# base.net
KiCad netlist of a schematic drawn in Altium Designer
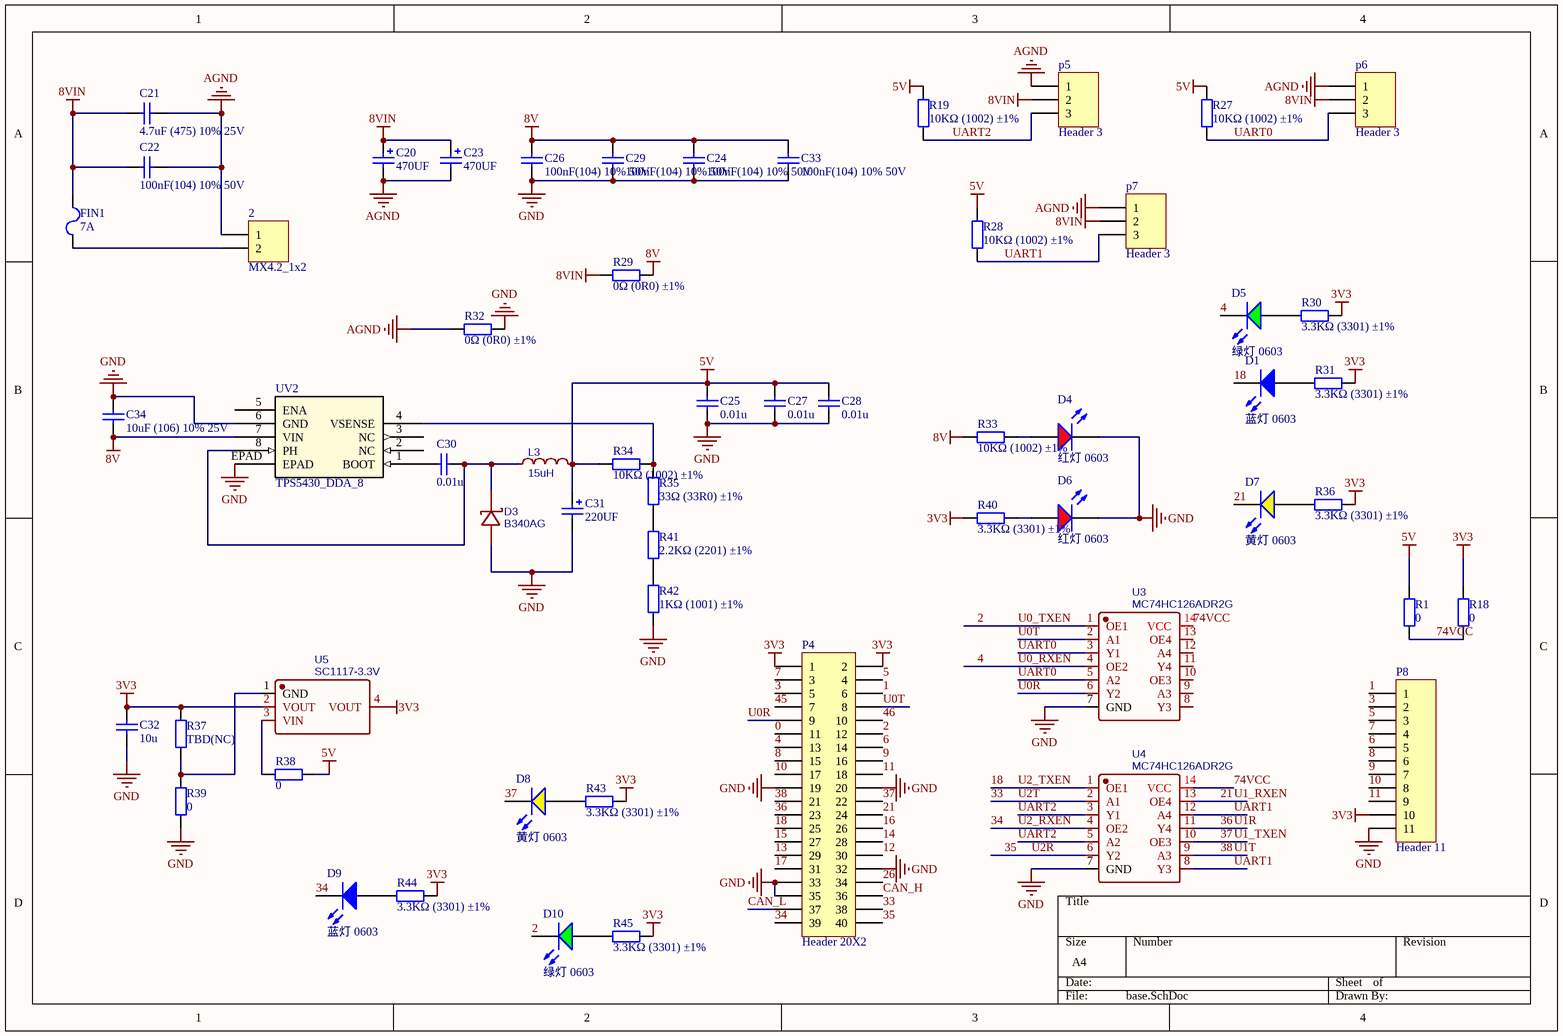
[diagram p0: base.SchDoc]

(export (version "E")
  (design (tool "Eeschema 10.0.6"))
  (components
    (comp (ref "2") (value "MX4.2_1x2") (footprint "MX4.2_1x2") (libsource (lib "Schlib") (part "MX4.2_1x2")))
    (comp (ref "C20")
      (value "470UF")
      (footprint "CAP-SMD_BD8.0-L8.3-W8.3-LS9.0-FD")
      (libsource (lib "Schlib") (part "C_RB-470UF/25V_5X10"))
    )
    (comp (ref "C21")
      (value "4.7uF (475) 10% 25V")
      (footprint "LC-0805_C")
      (description "贴片电容")
      (libsource (lib "Miscellaneous Devices LC") (part "0805 4.7uF (475) 10% 25V"))
    )
    (comp (ref "C22")
      (value "100nF(104) 10% 50V")
      (footprint "LC-0805_C")
      (description "贴片电容")
      (libsource (lib "Miscellaneous Devices LC") (part "0805 100nF(104) 10% 50V"))
    )
    (comp (ref "C23")
      (value "470UF")
      (footprint "CAP-SMD_BD8.0-L8.3-W8.3-LS9.0-FD")
      (libsource (lib "Schlib") (part "C_RB-470UF/25V_5X10"))
    )
    (comp (ref "C24")
      (value "100nF(104) 10% 50V")
      (footprint "LC-0805_C")
      (description "贴片电容")
      (libsource (lib "Miscellaneous Devices LC") (part "0805 100nF(104) 10% 50V"))
    )
    (comp (ref "C25") (value "0.01u") (footprint "C0603") (libsource (lib "Schlib") (part "CAP_0805")))
    (comp (ref "C26")
      (value "100nF(104) 10% 50V")
      (footprint "LC-0805_C")
      (description "贴片电容")
      (libsource (lib "Miscellaneous Devices LC") (part "0805 100nF(104) 10% 50V"))
    )
    (comp (ref "C27") (value "0.01u") (footprint "C0603") (libsource (lib "Schlib") (part "CAP_0805")))
    (comp (ref "C28") (value "0.01u") (footprint "C0603") (libsource (lib "Schlib") (part "CAP_0805")))
    (comp (ref "C29")
      (value "100nF(104) 10% 50V")
      (footprint "LC-0805_C")
      (description "贴片电容")
      (libsource (lib "Miscellaneous Devices LC") (part "0805 100nF(104) 10% 50V"))
    )
    (comp (ref "C30") (value "0.01u") (footprint "C0603") (libsource (lib "Schlib") (part "CAP_0805")))
    (comp (ref "C31")
      (value "220UF")
      (footprint "SMD,6.3x7.7mm")
      (libsource (lib "Schlib") (part "C_RB-470UF/25V_5X10"))
    )
    (comp (ref "C32") (value "10u") (footprint "C0603") (libsource (lib "Schlib") (part "CAP_0805")))
    (comp (ref "C33")
      (value "100nF(104) 10% 50V")
      (footprint "LC-0805_C")
      (description "贴片电容")
      (libsource (lib "Miscellaneous Devices LC") (part "0805 100nF(104) 10% 50V"))
    )
    (comp (ref "C34")
      (value "10uF (106) 10% 25V")
      (footprint "LC-0805_C")
      (description "贴片电容")
      (libsource (lib "Miscellaneous Devices LC") (part "0805 10uF (106) 10% 25V"))
    )
    (comp (ref "D1")
      (value "蓝灯 0603")
      (footprint "LC-0603_LED_S1")
      (description "发光二极管")
      (libsource (lib "Miscellaneous Devices LC") (part "0603 蓝灯"))
    )
    (comp (ref "D3")
      (value "B340AG")
      (footprint "SMA_L4.4-W2.6-LS5.0-RD")
      (fields (field (name "BOM_SUPPLIER PART") "C433997") (field (name "CONTRIBUTOR") "LCSC"))
      (libsource (lib "altium-import") (part "root_3_B340AG_"))
    )
    (comp (ref "D4")
      (value "红灯 0603")
      (footprint "LC-0603_LED_S1")
      (description "发光二极管")
      (libsource (lib "Miscellaneous Devices LC") (part "0603 红灯"))
    )
    (comp (ref "D5")
      (value "绿灯 0603")
      (footprint "LC-0603_LED_S1")
      (description "发光二极管")
      (libsource (lib "Miscellaneous Devices LC") (part "0603 绿灯"))
    )
    (comp (ref "D6")
      (value "红灯 0603")
      (footprint "LC-0603_LED_S1")
      (description "发光二极管")
      (libsource (lib "Miscellaneous Devices LC") (part "0603 红灯"))
    )
    (comp (ref "D7")
      (value "黄灯 0603")
      (footprint "LC-0603_LED_S1")
      (description "发光二极管")
      (libsource (lib "Miscellaneous Devices LC") (part "0603 黄灯"))
    )
    (comp (ref "D8")
      (value "黄灯 0603")
      (footprint "LC-0603_LED_S1")
      (description "发光二极管")
      (libsource (lib "Miscellaneous Devices LC") (part "0603 黄灯"))
    )
    (comp (ref "D9")
      (value "蓝灯 0603")
      (footprint "LC-0603_LED_S1")
      (description "发光二极管")
      (libsource (lib "Miscellaneous Devices LC") (part "0603 蓝灯"))
    )
    (comp (ref "D10")
      (value "绿灯 0603")
      (footprint "LC-0603_LED_S1")
      (description "发光二极管")
      (libsource (lib "Miscellaneous Devices LC") (part "0603 绿灯"))
    )
    (comp (ref "FIN1") (value "7A") (footprint "2512") (libsource (lib "Schlib") (part "Fuse")))
    (comp (ref "L3")
      (value "15uH")
      (footprint "电感")
      (fields
        (field (name "BOM_SUPPLIER PART") "C354559")
        (field (name "BOM_MANUFACTURER PART") "CKCS3012-15uH/M")
        (field (name "CONTRIBUTOR") "LCSC")
      )
      (libsource (lib "PCB_Project") (part "15uH"))
    )
    (comp (ref "P4")
      (value "Header 20X2")
      (footprint "ESP-BORD")
      (description "Header, 20-Pin, Dual row")
      (fields (field (name "PUBLISHER") "Altium Limited"))
      (libsource (lib "Miscellaneous Connectors") (part "Header 20X2"))
    )
    (comp (ref "p5")
      (value "Header 3")
      (footprint "PH2.0-LI-3P")
      (description "Header, 3-Pin")
      (fields (field (name "PUBLISHER") "Altium Limited"))
      (libsource (lib "Miscellaneous Connectors") (part "Header 3"))
    )
    (comp (ref "p6")
      (value "Header 3")
      (footprint "PH2.0-LI-3P")
      (description "Header, 3-Pin")
      (fields (field (name "PUBLISHER") "Altium Limited"))
      (libsource (lib "Miscellaneous Connectors") (part "Header 3"))
    )
    (comp (ref "p7")
      (value "Header 3")
      (footprint "PH2.0-LI-3P")
      (description "Header, 3-Pin")
      (fields (field (name "PUBLISHER") "Altium Limited"))
      (libsource (lib "Miscellaneous Connectors") (part "Header 3"))
    )
    (comp (ref "P8")
      (value "Header 11")
      (footprint "HDR1X11")
      (description "Header, 11-Pin")
      (fields (field (name "PUBLISHER") "Altium Limited"))
      (libsource (lib "Miscellaneous Connectors") (part "Header 11"))
    )
    (comp (ref "R1") (value "0") (footprint "R0603") (libsource (lib "Schlib") (part "RES_0805")))
    (comp (ref "R18") (value "0") (footprint "R0603") (libsource (lib "Schlib") (part "RES_0805")))
    (comp (ref "R19")
      (value "10KΩ (1002) ±1%")
      (footprint "LC-0402_R")
      (description "贴片电阻")
      (libsource (lib "Miscellaneous Devices LC") (part "0402 10KΩ (1002) 1%"))
    )
    (comp (ref "R27")
      (value "10KΩ (1002) ±1%")
      (footprint "LC-0402_R")
      (description "贴片电阻")
      (libsource (lib "") (part "0402 10KΩ (1002) 1%_2"))
    )
    (comp (ref "R28")
      (value "10KΩ (1002) ±1%")
      (footprint "LC-0402_R")
      (description "贴片电阻")
      (libsource (lib "") (part "0402 10KΩ (1002) 1%_2"))
    )
    (comp (ref "R29")
      (value "0Ω (0R0) ±1%")
      (footprint "LC-0805_R")
      (description "贴片电阻")
      (libsource (lib "Miscellaneous Devices LC") (part "0805 0Ω (0R0) 1%"))
    )
    (comp (ref "R30")
      (value "3.3KΩ (3301) ±1%")
      (footprint "LC-0402_R")
      (description "贴片电阻")
      (libsource (lib "Miscellaneous Devices LC") (part "0402 3.3KΩ (3301) 1%"))
    )
    (comp (ref "R31")
      (value "3.3KΩ (3301) ±1%")
      (footprint "LC-0402_R")
      (description "贴片电阻")
      (libsource (lib "Miscellaneous Devices LC") (part "0402 3.3KΩ (3301) 1%"))
    )
    (comp (ref "R32")
      (value "0Ω (0R0) ±1%")
      (footprint "LC-0805_R")
      (description "贴片电阻")
      (libsource (lib "Miscellaneous Devices LC") (part "0805 0Ω (0R0) 1%"))
    )
    (comp (ref "R33")
      (value "10KΩ (1002) ±1%")
      (footprint "LC-0402_R")
      (description "贴片电阻")
      (libsource (lib "") (part "0402 10KΩ (1002) 1%_1"))
    )
    (comp (ref "R34")
      (value "10KΩ (1002) ±1%")
      (footprint "LC-0805_R")
      (description "贴片电阻")
      (libsource (lib "Miscellaneous Devices LC") (part "0805 10KΩ (1002) 1%"))
    )
    (comp (ref "R35")
      (value "33Ω (33R0) ±1%")
      (footprint "LC-0805_R")
      (description "贴片电阻")
      (libsource (lib "Miscellaneous Devices LC") (part "0805 33Ω (33R0) 1%"))
    )
    (comp (ref "R36")
      (value "3.3KΩ (3301) ±1%")
      (footprint "LC-0402_R")
      (description "贴片电阻")
      (libsource (lib "Miscellaneous Devices LC") (part "0402 3.3KΩ (3301) 1%"))
    )
    (comp (ref "R37") (value "TBD(NC)") (footprint "R0603") (libsource (lib "") (part "RES_0805_1")))
    (comp (ref "R38") (value "0") (footprint "R0603") (libsource (lib "") (part "RES_0805_2")))
    (comp (ref "R39") (value "0") (footprint "R0603") (libsource (lib "Schlib") (part "RES_0805")))
    (comp (ref "R40")
      (value "3.3KΩ (3301) ±1%")
      (footprint "LC-0402_R")
      (description "贴片电阻")
      (libsource (lib "Miscellaneous Devices LC") (part "0402 3.3KΩ (3301) 1%"))
    )
    (comp (ref "R41")
      (value "2.2KΩ (2201) ±1%")
      (footprint "LC-0805_R")
      (description "贴片电阻")
      (libsource (lib "Miscellaneous Devices LC") (part "0805 2.2KΩ (2201) 1%"))
    )
    (comp (ref "R42")
      (value "1KΩ (1001) ±1%")
      (footprint "LC-0805_R")
      (description "贴片电阻")
      (libsource (lib "Miscellaneous Devices LC") (part "0805 1KΩ (1001) 1%"))
    )
    (comp (ref "R43")
      (value "3.3KΩ (3301) ±1%")
      (footprint "LC-0402_R")
      (description "贴片电阻")
      (libsource (lib "Miscellaneous Devices LC") (part "0402 3.3KΩ (3301) 1%"))
    )
    (comp (ref "R44")
      (value "3.3KΩ (3301) ±1%")
      (footprint "LC-0402_R")
      (description "贴片电阻")
      (libsource (lib "Miscellaneous Devices LC") (part "0402 3.3KΩ (3301) 1%"))
    )
    (comp (ref "R45")
      (value "3.3KΩ (3301) ±1%")
      (footprint "LC-0402_R")
      (description "贴片电阻")
      (libsource (lib "Miscellaneous Devices LC") (part "0402 3.3KΩ (3301) 1%"))
    )
    (comp (ref "U3")
      (value "MC74HC126ADR2G")
      (footprint "SOIC-14_L8.7-W3.9-P1.27-LS6.0-BL")
      (fields (field (name "BOM_SUPPLIER PART") "C233530") (field (name "CONTRIBUTOR") "LCSC"))
      (libsource (lib "altium-import") (part "root_0_MC74HC126ADR2G_"))
    )
    (comp (ref "U4")
      (value "MC74HC126ADR2G")
      (footprint "SOIC-14_L8.7-W3.9-P1.27-LS6.0-BL")
      (fields (field (name "BOM_SUPPLIER PART") "C233530") (field (name "CONTRIBUTOR") "LCSC"))
      (libsource (lib "altium-import") (part "root_0_MC74HC126ADR2G_"))
    )
    (comp (ref "U5")
      (value "SC1117-3.3V")
      (footprint "SOT-223_L6.5-W3.5-P2.30-LS7.0-BR")
      (fields (field (name "BOM_SUPPLIER PART") "C173386") (field (name "CONTRIBUTOR") "LCSC"))
      (libsource (lib "altium-import") (part "root_0_SC1117-3.3V_"))
    )
    (comp (ref "UV2")
      (value "TPS5430_DDA_8")
      (footprint "DDA8_3P1X2P4")
      (description "Imported")
      (fields
        (field (name "MANUFACTURER_PART_NUMBER") "tps5430_dda_8")
        (field (name "GENERIC_PART_NUMBER") "TPS5430")
      )
      (libsource (lib "TPS5430") (part "TPS5430_DDA_8"))
    )
  )
  (nets
    (net (code "1") (name "/0") (class "Default")
      (node (ref "P4") (pin "11") (pinfunction "11_11") (pintype "passive"))
    )
    (net (code "2") (name "/1") (class "Default")
      (node (ref "P4") (pin "6") (pinfunction "6_6") (pintype "passive"))
      (node (ref "P8") (pin "1") (pinfunction "1_1") (pintype "passive"))
    )
    (net (code "3") (name "/2") (class "Default")
      (node (ref "D10") (pin "K") (pinfunction "K_K") (pintype "passive"))
      (node (ref "P4") (pin "12") (pinfunction "12_12") (pintype "passive"))
      (node (ref "U3") (pin "1") (pinfunction "OE1_1") (pintype "passive"))
    )
    (net (code "4") (name "/3") (class "Default")
      (node (ref "P4") (pin "5") (pinfunction "5_5") (pintype "passive"))
      (node (ref "P8") (pin "2") (pinfunction "2_2") (pintype "passive"))
    )
    (net (code "5") (name "/4") (class "Default")
      (node (ref "D5") (pin "K") (pinfunction "K_K") (pintype "passive"))
      (node (ref "P4") (pin "13") (pinfunction "13_13") (pintype "passive"))
      (node (ref "U3") (pin "4") (pinfunction "OE2_4") (pintype "passive"))
    )
    (net (code "6") (name "/5") (class "Default")
      (node (ref "P4") (pin "4") (pinfunction "4_4") (pintype "passive"))
      (node (ref "P8") (pin "3") (pinfunction "3_3") (pintype "passive"))
    )
    (net (code "7") (name "/6") (class "Default")
      (node (ref "P4") (pin "14") (pinfunction "14_14") (pintype "passive"))
      (node (ref "P8") (pin "5") (pinfunction "5_5") (pintype "passive"))
    )
    (net (code "8") (name "/7") (class "Default")
      (node (ref "P4") (pin "3") (pinfunction "3_3") (pintype "passive"))
      (node (ref "P8") (pin "4") (pinfunction "4_4") (pintype "passive"))
    )
    (net (code "9") (name "/8") (class "Default")
      (node (ref "P4") (pin "15") (pinfunction "15_15") (pintype "passive"))
      (node (ref "P8") (pin "6") (pinfunction "6_6") (pintype "passive"))
    )
    (net (code "10") (name "/9") (class "Default")
      (node (ref "P4") (pin "16") (pinfunction "16_16") (pintype "passive"))
      (node (ref "P8") (pin "7") (pinfunction "7_7") (pintype "passive"))
    )
    (net (code "11") (name "/10") (class "Default")
      (node (ref "P4") (pin "17") (pinfunction "17_17") (pintype "passive"))
      (node (ref "P8") (pin "8") (pinfunction "8_8") (pintype "passive"))
    )
    (net (code "12") (name "/11") (class "Default")
      (node (ref "P4") (pin "18") (pinfunction "18_18") (pintype "passive"))
      (node (ref "P8") (pin "9") (pinfunction "9_9") (pintype "passive"))
    )
    (net (code "13") (name "/12") (class "Default")
      (node (ref "P4") (pin "30") (pinfunction "30_30") (pintype "passive"))
    )
    (net (code "14") (name "/13") (class "Default")
      (node (ref "P4") (pin "29") (pinfunction "29_29") (pintype "passive"))
    )
    (net (code "15") (name "/14") (class "Default")
      (node (ref "P4") (pin "28") (pinfunction "28_28") (pintype "passive"))
    )
    (net (code "16") (name "/15") (class "Default")
      (node (ref "P4") (pin "27") (pinfunction "27_27") (pintype "passive"))
    )
    (net (code "17") (name "/16") (class "Default")
      (node (ref "P4") (pin "26") (pinfunction "26_26") (pintype "passive"))
    )
    (net (code "18") (name "/17") (class "Default")
      (node (ref "P4") (pin "31") (pinfunction "31_31") (pintype "passive"))
    )
    (net (code "19") (name "/18") (class "Default")
      (node (ref "D1") (pin "K") (pinfunction "K_K") (pintype "passive"))
      (node (ref "P4") (pin "25") (pinfunction "25_25") (pintype "passive"))
      (node (ref "U4") (pin "1") (pinfunction "OE1_1") (pintype "passive"))
    )
    (net (code "20") (name "/21") (class "Default")
      (node (ref "D7") (pin "K") (pinfunction "K_K") (pintype "passive"))
      (node (ref "P4") (pin "24") (pinfunction "24_24") (pintype "passive"))
      (node (ref "U4") (pin "13") (pinfunction "OE4_13") (pintype "passive"))
    )
    (net (code "21") (name "/26") (class "Default")
      (node (ref "P4") (pin "34") (pinfunction "34_34") (pintype "passive"))
    )
    (net (code "22") (name "/33") (class "Default")
      (node (ref "P4") (pin "38") (pinfunction "38_38") (pintype "passive"))
      (node (ref "U4") (pin "2") (pinfunction "A1_2") (pintype "passive"))
    )
    (net (code "23") (name "/34") (class "Default")
      (node (ref "D9") (pin "K") (pinfunction "K_K") (pintype "passive"))
      (node (ref "P4") (pin "39") (pinfunction "39_39") (pintype "passive"))
      (node (ref "U4") (pin "4") (pinfunction "OE2_4") (pintype "passive"))
    )
    (net (code "24") (name "/35") (class "Default")
      (node (ref "P4") (pin "40") (pinfunction "40_40") (pintype "passive"))
      (node (ref "U4") (pin "6") (pinfunction "Y2_6") (pintype "passive"))
    )
    (net (code "25") (name "/36") (class "Default")
      (node (ref "P4") (pin "23") (pinfunction "23_23") (pintype "passive"))
      (node (ref "U4") (pin "11") (pinfunction "Y4_11") (pintype "passive"))
    )
    (net (code "26") (name "/37") (class "Default")
      (node (ref "D8") (pin "K") (pinfunction "K_K") (pintype "passive"))
      (node (ref "P4") (pin "22") (pinfunction "22_22") (pintype "passive"))
      (node (ref "U4") (pin "10") (pinfunction "OE3_10") (pintype "passive"))
    )
    (net (code "27") (name "/38") (class "Default")
      (node (ref "P4") (pin "21") (pinfunction "21_21") (pintype "passive"))
      (node (ref "U4") (pin "9") (pinfunction "A3_9") (pintype "passive"))
    )
    (net (code "28") (name "/45") (class "Default")
      (node (ref "P4") (pin "7") (pinfunction "7_7") (pintype "passive"))
    )
    (net (code "29") (name "/46") (class "Default")
      (node (ref "P4") (pin "10") (pinfunction "10_10") (pintype "passive"))
    )
    (net (code "30") (name "/74VCC") (class "Default")
      (node (ref "R1") (pin "1") (pinfunction "1_1") (pintype "passive"))
      (node (ref "R18") (pin "1") (pinfunction "1_1") (pintype "passive"))
      (node (ref "U3") (pin "14") (pinfunction "VCC_14") (pintype "passive"))
      (node (ref "U4") (pin "14") (pinfunction "VCC_14") (pintype "passive"))
    )
    (net (code "31") (name "/CAN_H") (class "Default")
      (node (ref "P4") (pin "36") (pinfunction "36_36") (pintype "passive"))
    )
    (net (code "32") (name "/CAN_L") (class "Default")
      (node (ref "P4") (pin "37") (pinfunction "37_37") (pintype "passive"))
    )
    (net (code "33") (name "/U0R") (class "Default")
      (node (ref "P4") (pin "9") (pinfunction "9_9") (pintype "passive"))
      (node (ref "U3") (pin "6") (pinfunction "Y2_6") (pintype "passive"))
    )
    (net (code "34") (name "/U0T") (class "Default")
      (node (ref "P4") (pin "8") (pinfunction "8_8") (pintype "passive"))
      (node (ref "U3") (pin "2") (pinfunction "A1_2") (pintype "passive"))
    )
    (net (code "35") (name "/UART0") (class "Default")
      (node (ref "R27") (pin "1") (pinfunction "1_1") (pintype "passive"))
      (node (ref "U3") (pin "3") (pinfunction "Y1_3") (pintype "passive"))
      (node (ref "U3") (pin "5") (pinfunction "A2_5") (pintype "passive"))
      (node (ref "p6") (pin "3") (pinfunction "3_3") (pintype "passive"))
    )
    (net (code "36") (name "/UART1") (class "Default")
      (node (ref "R28") (pin "1") (pinfunction "1_1") (pintype "passive"))
      (node (ref "U4") (pin "12") (pinfunction "A4_12") (pintype "passive"))
      (node (ref "U4") (pin "8") (pinfunction "Y3_8") (pintype "passive"))
      (node (ref "p7") (pin "3") (pinfunction "3_3") (pintype "passive"))
    )
    (net (code "37") (name "/UART2") (class "Default")
      (node (ref "R19") (pin "2") (pinfunction "2_2") (pintype "passive"))
      (node (ref "U4") (pin "3") (pinfunction "Y1_3") (pintype "passive"))
      (node (ref "U4") (pin "5") (pinfunction "A2_5") (pintype "passive"))
      (node (ref "p5") (pin "3") (pinfunction "3_3") (pintype "passive"))
    )
    (net (code "38") (name "3V3") (class "Default")
      (node (ref "C32") (pin "2") (pinfunction "2_2") (pintype "passive"))
      (node (ref "P4") (pin "1") (pinfunction "1_1") (pintype "passive"))
      (node (ref "P4") (pin "2") (pinfunction "2_2") (pintype "passive"))
      (node (ref "P8") (pin "10") (pinfunction "10_10") (pintype "passive"))
      (node (ref "R18") (pin "2") (pinfunction "2_2") (pintype "passive"))
      (node (ref "R30") (pin "2") (pinfunction "2_2") (pintype "passive"))
      (node (ref "R31") (pin "2") (pinfunction "2_2") (pintype "passive"))
      (node (ref "R36") (pin "2") (pinfunction "2_2") (pintype "passive"))
      (node (ref "R37") (pin "1") (pinfunction "1_1") (pintype "passive"))
      (node (ref "R40") (pin "1") (pinfunction "1_1") (pintype "passive"))
      (node (ref "R43") (pin "2") (pinfunction "2_2") (pintype "passive"))
      (node (ref "R44") (pin "2") (pinfunction "2_2") (pintype "passive"))
      (node (ref "R45") (pin "2") (pinfunction "2_2") (pintype "passive"))
      (node (ref "U5") (pin "2") (pinfunction "VOUT_2") (pintype "passive"))
      (node (ref "U5") (pin "4") (pinfunction "VOUT_4") (pintype "passive"))
    )
    (net (code "39") (name "5V") (class "Default")
      (node (ref "C25") (pin "1") (pinfunction "1_1") (pintype "passive"))
      (node (ref "C27") (pin "1") (pinfunction "1_1") (pintype "passive"))
      (node (ref "C28") (pin "2") (pinfunction "2_2") (pintype "passive"))
      (node (ref "C31") (pin "1") (pinfunction "1_1") (pintype "passive"))
      (node (ref "L3") (pin "2") (pinfunction "2_2") (pintype "passive"))
      (node (ref "R1") (pin "2") (pinfunction "2_2") (pintype "passive"))
      (node (ref "R19") (pin "1") (pinfunction "1_1") (pintype "passive"))
      (node (ref "R27") (pin "2") (pinfunction "2_2") (pintype "passive"))
      (node (ref "R28") (pin "2") (pinfunction "2_2") (pintype "passive"))
      (node (ref "R34") (pin "1") (pinfunction "1_1") (pintype "passive"))
      (node (ref "R38") (pin "1") (pinfunction "1_1") (pintype "passive"))
    )
    (net (code "40") (name "8V") (class "Default")
      (node (ref "C24") (pin "2") (pinfunction "2_2") (pintype "passive"))
      (node (ref "C26") (pin "2") (pinfunction "2_2") (pintype "passive"))
      (node (ref "C29") (pin "2") (pinfunction "2_2") (pintype "passive"))
      (node (ref "C33") (pin "2") (pinfunction "2_2") (pintype "passive"))
      (node (ref "C34") (pin "1") (pinfunction "1_1") (pintype "passive"))
      (node (ref "R29") (pin "2") (pinfunction "2_2") (pintype "passive"))
      (node (ref "R33") (pin "1") (pinfunction "1_1") (pintype "passive"))
      (node (ref "UV2") (pin "7") (pinfunction "VIN_7") (pintype "passive"))
    )
    (net (code "41") (name "8VIN") (class "Default")
      (node (ref "C20") (pin "1") (pinfunction "1_1") (pintype "passive"))
      (node (ref "C21") (pin "1") (pinfunction "1_1") (pintype "passive"))
      (node (ref "C22") (pin "1") (pinfunction "1_1") (pintype "passive"))
      (node (ref "C23") (pin "1") (pinfunction "1_1") (pintype "passive"))
      (node (ref "FIN1") (pin "2") (pinfunction "2_2") (pintype "passive"))
      (node (ref "R29") (pin "1") (pinfunction "1_1") (pintype "passive"))
      (node (ref "p5") (pin "2") (pinfunction "2_2") (pintype "passive"))
      (node (ref "p6") (pin "2") (pinfunction "2_2") (pintype "passive"))
      (node (ref "p7") (pin "2") (pinfunction "2_2") (pintype "passive"))
    )
    (net (code "42") (name "AGND") (class "Default")
      (node (ref "2") (pin "1") (pinfunction "1_1") (pintype "passive"))
      (node (ref "C20") (pin "2") (pinfunction "2_2") (pintype "passive"))
      (node (ref "C21") (pin "2") (pinfunction "2_2") (pintype "passive"))
      (node (ref "C22") (pin "2") (pinfunction "2_2") (pintype "passive"))
      (node (ref "C23") (pin "2") (pinfunction "2_2") (pintype "passive"))
      (node (ref "R32") (pin "1") (pinfunction "1_1") (pintype "passive"))
      (node (ref "p5") (pin "1") (pinfunction "1_1") (pintype "passive"))
      (node (ref "p6") (pin "1") (pinfunction "1_1") (pintype "passive"))
      (node (ref "p7") (pin "1") (pinfunction "1_1") (pintype "passive"))
    )
    (net (code "43") (name "GND") (class "Default")
      (node (ref "C24") (pin "1") (pinfunction "1_1") (pintype "passive"))
      (node (ref "C25") (pin "2") (pinfunction "2_2") (pintype "passive"))
      (node (ref "C26") (pin "1") (pinfunction "1_1") (pintype "passive"))
      (node (ref "C27") (pin "2") (pinfunction "2_2") (pintype "passive"))
      (node (ref "C28") (pin "1") (pinfunction "1_1") (pintype "passive"))
      (node (ref "C29") (pin "1") (pinfunction "1_1") (pintype "passive"))
      (node (ref "C31") (pin "2") (pinfunction "2_2") (pintype "passive"))
      (node (ref "C32") (pin "1") (pinfunction "1_1") (pintype "passive"))
      (node (ref "C33") (pin "1") (pinfunction "1_1") (pintype "passive"))
      (node (ref "C34") (pin "2") (pinfunction "2_2") (pintype "passive"))
      (node (ref "D3") (pin "2") (pinfunction "A_2") (pintype "passive"))
      (node (ref "D4") (pin "K") (pinfunction "K_K") (pintype "passive"))
      (node (ref "D6") (pin "K") (pinfunction "K_K") (pintype "passive"))
      (node (ref "P4") (pin "19") (pinfunction "19_19") (pintype "passive"))
      (node (ref "P4") (pin "20") (pinfunction "20_20") (pintype "passive"))
      (node (ref "P4") (pin "32") (pinfunction "32_32") (pintype "passive"))
      (node (ref "P4") (pin "33") (pinfunction "33_33") (pintype "passive"))
      (node (ref "P4") (pin "35") (pinfunction "35_35") (pintype "passive"))
      (node (ref "P8") (pin "11") (pinfunction "11_11") (pintype "passive"))
      (node (ref "R32") (pin "2") (pinfunction "2_2") (pintype "passive"))
      (node (ref "R39") (pin "1") (pinfunction "1_1") (pintype "passive"))
      (node (ref "R42") (pin "1") (pinfunction "1_1") (pintype "passive"))
      (node (ref "U3") (pin "7") (pinfunction "GND_7") (pintype "passive"))
      (node (ref "U4") (pin "7") (pinfunction "GND_7") (pintype "passive"))
      (node (ref "UV2") (pin "6") (pinfunction "GND_6") (pintype "passive"))
      (node (ref "UV2") (pin "EPAD") (pinfunction "EPAD_EPAD") (pintype "passive"))
    )
    (net (code "44") (name "Net-(2-Pad2)") (class "Default")
      (node (ref "2") (pin "2") (pinfunction "2_2") (pintype "passive"))
      (node (ref "FIN1") (pin "1") (pinfunction "1_1") (pintype "passive"))
    )
    (net (code "45") (name "Net-(D1-PadA)") (class "Default")
      (node (ref "D1") (pin "A") (pinfunction "A_A") (pintype "passive"))
      (node (ref "R31") (pin "1") (pinfunction "1_1") (pintype "passive"))
    )
    (net (code "46") (name "Net-(D3-C)") (class "Default")
      (node (ref "C30") (pin "2") (pinfunction "2_2") (pintype "passive"))
      (node (ref "D3") (pin "1") (pinfunction "C_1") (pintype "passive"))
      (node (ref "L3") (pin "1") (pinfunction "1_1") (pintype "passive"))
      (node (ref "UV2") (pin "8") (pinfunction "PH_8") (pintype "input"))
    )
    (net (code "47") (name "Net-(D4-PadA)") (class "Default")
      (node (ref "D4") (pin "A") (pinfunction "A_A") (pintype "passive"))
      (node (ref "R33") (pin "2") (pinfunction "2_2") (pintype "passive"))
    )
    (net (code "48") (name "Net-(D5-PadA)") (class "Default")
      (node (ref "D5") (pin "A") (pinfunction "A_A") (pintype "passive"))
      (node (ref "R30") (pin "1") (pinfunction "1_1") (pintype "passive"))
    )
    (net (code "49") (name "Net-(D6-PadA)") (class "Default")
      (node (ref "D6") (pin "A") (pinfunction "A_A") (pintype "passive"))
      (node (ref "R40") (pin "2") (pinfunction "2_2") (pintype "passive"))
    )
    (net (code "50") (name "Net-(D7-PadA)") (class "Default")
      (node (ref "D7") (pin "A") (pinfunction "A_A") (pintype "passive"))
      (node (ref "R36") (pin "1") (pinfunction "1_1") (pintype "passive"))
    )
    (net (code "51") (name "Net-(D8-PadA)") (class "Default")
      (node (ref "D8") (pin "A") (pinfunction "A_A") (pintype "passive"))
      (node (ref "R43") (pin "1") (pinfunction "1_1") (pintype "passive"))
    )
    (net (code "52") (name "Net-(D9-PadA)") (class "Default")
      (node (ref "D9") (pin "A") (pinfunction "A_A") (pintype "passive"))
      (node (ref "R44") (pin "1") (pinfunction "1_1") (pintype "passive"))
    )
    (net (code "53") (name "Net-(D10-PadA)") (class "Default")
      (node (ref "D10") (pin "A") (pinfunction "A_A") (pintype "passive"))
      (node (ref "R45") (pin "1") (pinfunction "1_1") (pintype "passive"))
    )
    (net (code "54") (name "Net-(R35-Pad1)") (class "Default")
      (node (ref "R35") (pin "1") (pinfunction "1_1") (pintype "passive"))
      (node (ref "R41") (pin "2") (pinfunction "2_2") (pintype "passive"))
    )
    (net (code "55") (name "Net-(R41-Pad1)") (class "Default")
      (node (ref "R41") (pin "1") (pinfunction "1_1") (pintype "passive"))
      (node (ref "R42") (pin "2") (pinfunction "2_2") (pintype "passive"))
    )
    (net (code "56") (name "Net-(U5-GND)") (class "Default")
      (node (ref "R37") (pin "2") (pinfunction "2_2") (pintype "passive"))
      (node (ref "R39") (pin "2") (pinfunction "2_2") (pintype "passive"))
      (node (ref "U5") (pin "1") (pinfunction "GND_1") (pintype "passive"))
    )
    (net (code "57") (name "Net-(U5-VIN)") (class "Default")
      (node (ref "R38") (pin "2") (pinfunction "2_2") (pintype "passive"))
      (node (ref "U5") (pin "3") (pinfunction "VIN_3") (pintype "passive"))
    )
    (net (code "58") (name "Net-(UV2-BOOT)") (class "Default")
      (node (ref "C30") (pin "1") (pinfunction "1_1") (pintype "passive"))
      (node (ref "UV2") (pin "1") (pinfunction "BOOT_1") (pintype "input"))
    )
    (net (code "59") (name "Net-(UV2-VSENSE)") (class "Default")
      (node (ref "R34") (pin "2") (pinfunction "2_2") (pintype "passive"))
      (node (ref "R35") (pin "2") (pinfunction "2_2") (pintype "passive"))
      (node (ref "UV2") (pin "4") (pinfunction "VSENSE_4") (pintype "passive"))
    )
    (net (code "60") (name "unconnected-(U3-A3-Pad9)") (class "Default")
      (node (ref "U3") (pin "9") (pinfunction "A3_9") (pintype "passive"))
    )
    (net (code "61") (name "unconnected-(U3-A4-Pad12)") (class "Default")
      (node (ref "U3") (pin "12") (pinfunction "A4_12") (pintype "passive"))
    )
    (net (code "62") (name "unconnected-(U3-OE3-Pad10)") (class "Default")
      (node (ref "U3") (pin "10") (pinfunction "OE3_10") (pintype "passive"))
    )
    (net (code "63") (name "unconnected-(U3-OE4-Pad13)") (class "Default")
      (node (ref "U3") (pin "13") (pinfunction "OE4_13") (pintype "passive"))
    )
    (net (code "64") (name "unconnected-(U3-Y3-Pad8)") (class "Default")
      (node (ref "U3") (pin "8") (pinfunction "Y3_8") (pintype "passive"))
    )
    (net (code "65") (name "unconnected-(U3-Y4-Pad11)") (class "Default")
      (node (ref "U3") (pin "11") (pinfunction "Y4_11") (pintype "passive"))
    )
    (net (code "66") (name "unconnected-(UV2-ENA-Pad5)") (class "Default")
      (node (ref "UV2") (pin "5") (pinfunction "ENA_5") (pintype "power_in"))
    )
    (net (code "67") (name "unconnected-(UV2-NC-Pad2)") (class "Default")
      (node (ref "UV2") (pin "2") (pinfunction "NC_2") (pintype "input"))
    )
    (net (code "68") (name "unconnected-(UV2-NC-Pad3)") (class "Default")
      (node (ref "UV2") (pin "3") (pinfunction "NC_3") (pintype "output"))
    )
  )
)
